# 1-Schematic_SMALL_MODULE.net
KiCad netlist of a schematic drawn in EasyEDA
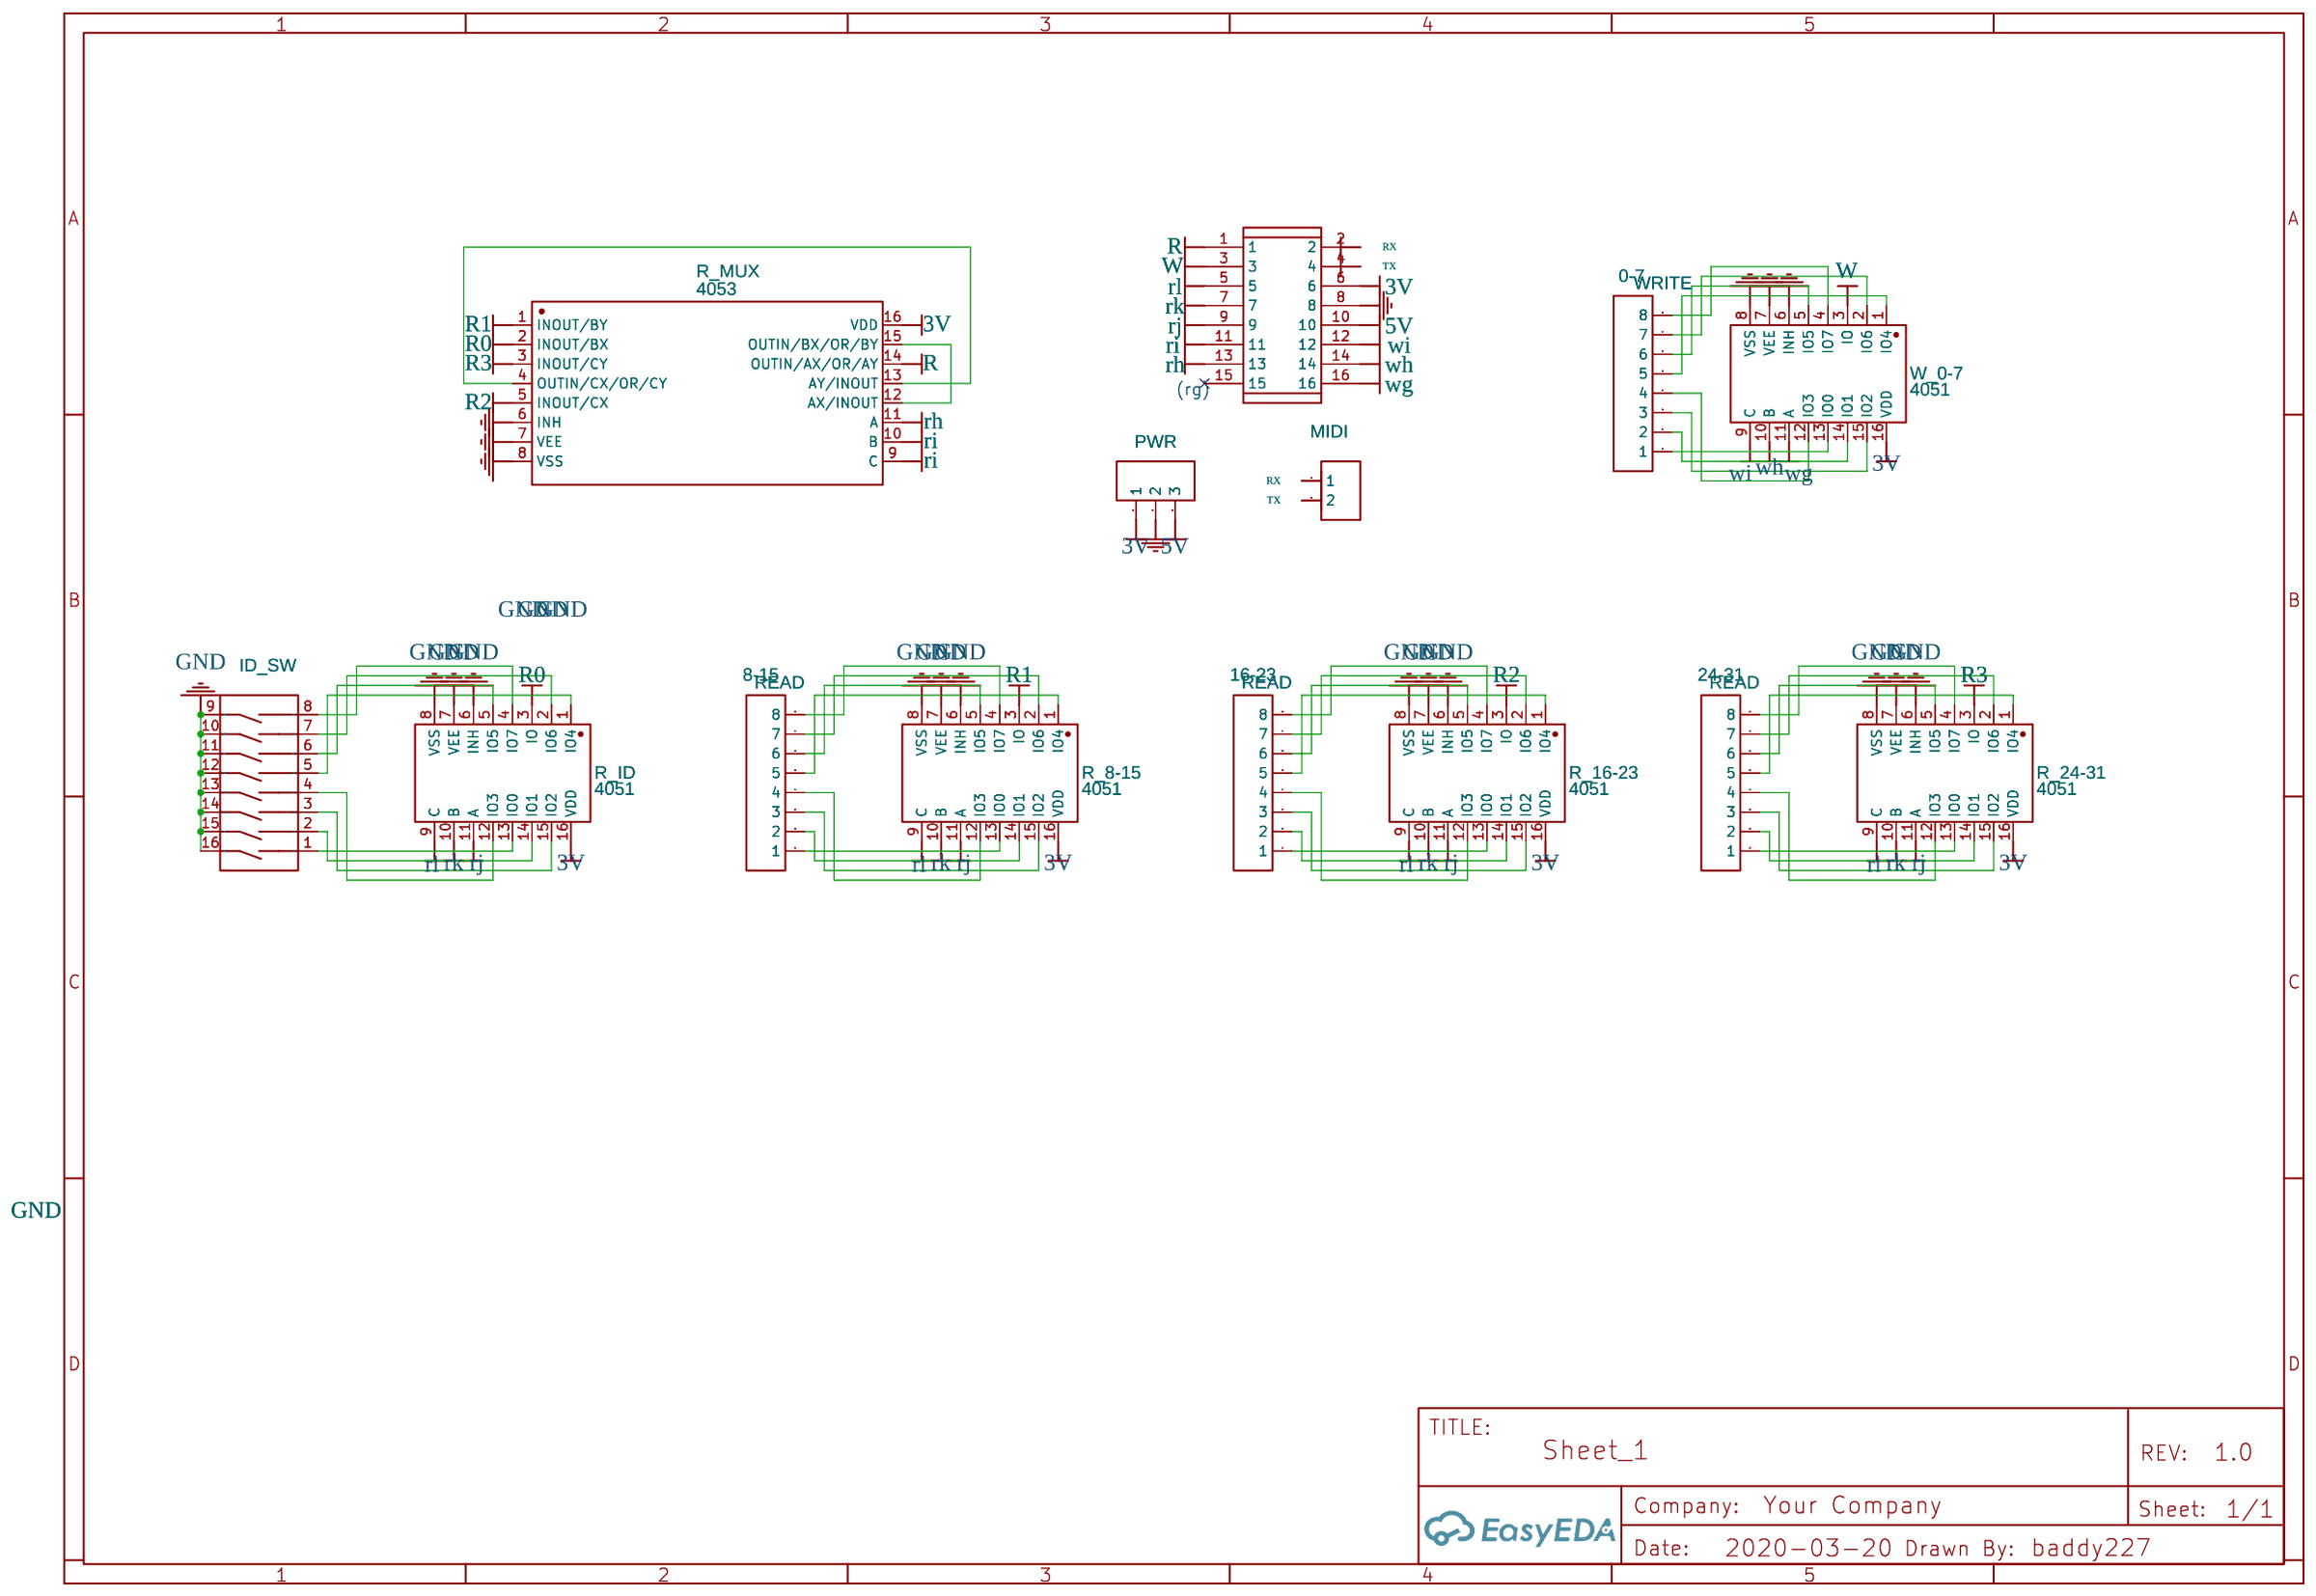
[diagram p0: schematic sheet]

(export (version "E")
  (design (tool "Eeschema 10.0.6"))
  (components
    (comp (ref "0-7")
      (value "WRITE")
      (fields
        (field (name "BOM_Manufacturer Part") "Female headerHDR1X8-2.54")
        (field (name "BOM_Supplier Part") "C27438")
      )
      (libsource (lib "") (part "Header-Female-2.54_1x8_1"))
    )
    (comp (ref "8-15")
      (value "READ")
      (fields
        (field (name "BOM_Manufacturer Part") "Female headerHDR1X8-2.54")
        (field (name "BOM_Supplier Part") "C27438")
      )
      (libsource (lib "") (part "Header-Female-2.54_1x8_2"))
    )
    (comp (ref "16-23")
      (value "READ")
      (fields
        (field (name "BOM_Manufacturer Part") "Female headerHDR1X8-2.54")
        (field (name "BOM_Supplier Part") "C27438")
      )
      (libsource (lib "") (part "Header-Female-2.54_1x8"))
    )
    (comp (ref "24-31")
      (value "READ")
      (fields
        (field (name "BOM_Manufacturer Part") "Female headerHDR1X8-2.54")
        (field (name "BOM_Supplier Part") "C27438")
      )
      (libsource (lib "") (part "Header-Female-2.54_1x8_3"))
    )
    (comp (ref "IDC_16")
      (value "IDC Box 2X8 2.54MM")
      (fields (field (name "BOM_Supplier Part") "C9142"))
      (libsource (lib "") (part "IDC Box 2X8 2.54MM"))
    )
    (comp (ref "ID_SW")
      (value "DIP switchEI-08")
      (fields (field (name "BOM_Supplier Part") "C90019"))
      (libsource (lib "") (part "DIP switchEI-08"))
    )
    (comp (ref "MIDI")
      (value "HDR-M-2.54_1x2")
      (fields (field (name "BOM_Supplier Part") "C124375"))
      (libsource (lib "") (part "HDR-M-2.54_1x2"))
    )
    (comp (ref "PWR")
      (value "Header-Male-2.54_1x3")
      (fields
        (field (name "BOM_Manufacturer Part") "Header2.54mm 1*3P")
        (field (name "BOM_Supplier Part") "C49257")
      )
      (libsource (lib "") (part "Header-Male-2.54_1x3"))
    )
    (comp (ref "R_8-15")
      (value "4051")
      (fields (field (name "BOM_Manufacturer Part") "CD4051BE") (field (name "BOM_Supplier Part") "C5200"))
      (libsource (lib "") (part "CD4051BE"))
    )
    (comp (ref "R_16-23")
      (value "4051")
      (fields (field (name "BOM_Manufacturer Part") "CD4051BE") (field (name "BOM_Supplier Part") "C5200"))
      (libsource (lib "") (part "CD4051BE_1"))
    )
    (comp (ref "R_24-31")
      (value "4051")
      (fields (field (name "BOM_Manufacturer Part") "CD4051BE") (field (name "BOM_Supplier Part") "C5200"))
      (libsource (lib "") (part "CD4051BE_3"))
    )
    (comp (ref "R_ID")
      (value "4051")
      (fields (field (name "BOM_Manufacturer Part") "CD4051BE") (field (name "BOM_Supplier Part") "C5200"))
      (libsource (lib "") (part "CD4051BE_4"))
    )
    (comp (ref "R_MUX")
      (value "4053")
      (fields (field (name "BOM_Manufacturer Part") "CD4053BE") (field (name "BOM_Supplier Part") "C5202"))
      (libsource (lib "") (part "CD4053BE"))
    )
    (comp (ref "W_0-7")
      (value "4051")
      (fields (field (name "BOM_Manufacturer Part") "CD4051BE") (field (name "BOM_Supplier Part") "C5200"))
      (libsource (lib "") (part "CD4051BE_2"))
    )
  )
  (nets
    (net (code "1") (name "3V") (class "Default")
      (node (ref "IDC_16") (pin "6") (pinfunction "6_6") (pintype "unspecified"))
      (node (ref "PWR") (pin "1") (pinfunction "1_1") (pintype "input"))
      (node (ref "R_16-23") (pin "16") (pinfunction "VDD_16") (pintype "unspecified"))
      (node (ref "R_24-31") (pin "16") (pinfunction "VDD_16") (pintype "unspecified"))
      (node (ref "R_8-15") (pin "16") (pinfunction "VDD_16") (pintype "unspecified"))
      (node (ref "R_ID") (pin "16") (pinfunction "VDD_16") (pintype "unspecified"))
      (node (ref "R_MUX") (pin "16") (pinfunction "VDD_16") (pintype "unspecified"))
      (node (ref "W_0-7") (pin "16") (pinfunction "VDD_16") (pintype "unspecified"))
    )
    (net (code "2") (name "5V") (class "Default")
      (node (ref "IDC_16") (pin "10") (pinfunction "10_10") (pintype "unspecified"))
      (node (ref "PWR") (pin "3") (pinfunction "3_3") (pintype "input"))
    )
    (net (code "3") (name "GND") (class "Default")
      (node (ref "IDC_16") (pin "8") (pinfunction "8_8") (pintype "unspecified"))
      (node (ref "ID_SW") (pin "10") (pinfunction "10_10") (pintype "unspecified"))
      (node (ref "ID_SW") (pin "11") (pinfunction "11_11") (pintype "unspecified"))
      (node (ref "ID_SW") (pin "12") (pinfunction "12_12") (pintype "unspecified"))
      (node (ref "ID_SW") (pin "13") (pinfunction "13_13") (pintype "unspecified"))
      (node (ref "ID_SW") (pin "14") (pinfunction "14_14") (pintype "unspecified"))
      (node (ref "ID_SW") (pin "15") (pinfunction "15_15") (pintype "unspecified"))
      (node (ref "ID_SW") (pin "16") (pinfunction "16_16") (pintype "unspecified"))
      (node (ref "ID_SW") (pin "9") (pinfunction "9_9") (pintype "unspecified"))
      (node (ref "PWR") (pin "2") (pinfunction "2_2") (pintype "input"))
      (node (ref "R_16-23") (pin "6") (pinfunction "INH_6") (pintype "unspecified"))
      (node (ref "R_16-23") (pin "7") (pinfunction "VEE_7") (pintype "unspecified"))
      (node (ref "R_16-23") (pin "8") (pinfunction "VSS_8") (pintype "unspecified"))
      (node (ref "R_24-31") (pin "6") (pinfunction "INH_6") (pintype "unspecified"))
      (node (ref "R_24-31") (pin "7") (pinfunction "VEE_7") (pintype "unspecified"))
      (node (ref "R_24-31") (pin "8") (pinfunction "VSS_8") (pintype "unspecified"))
      (node (ref "R_8-15") (pin "6") (pinfunction "INH_6") (pintype "unspecified"))
      (node (ref "R_8-15") (pin "7") (pinfunction "VEE_7") (pintype "unspecified"))
      (node (ref "R_8-15") (pin "8") (pinfunction "VSS_8") (pintype "unspecified"))
      (node (ref "R_ID") (pin "6") (pinfunction "INH_6") (pintype "unspecified"))
      (node (ref "R_ID") (pin "7") (pinfunction "VEE_7") (pintype "unspecified"))
      (node (ref "R_ID") (pin "8") (pinfunction "VSS_8") (pintype "unspecified"))
      (node (ref "R_MUX") (pin "6") (pinfunction "INH_6") (pintype "unspecified"))
      (node (ref "R_MUX") (pin "7") (pinfunction "VEE_7") (pintype "unspecified"))
      (node (ref "R_MUX") (pin "8") (pinfunction "VSS_8") (pintype "unspecified"))
      (node (ref "W_0-7") (pin "6") (pinfunction "INH_6") (pintype "unspecified"))
      (node (ref "W_0-7") (pin "7") (pinfunction "VEE_7") (pintype "unspecified"))
      (node (ref "W_0-7") (pin "8") (pinfunction "VSS_8") (pintype "unspecified"))
    )
    (net (code "4") (name "Net-(R_8-15-IO0)") (class "Default")
      (node (ref "8-15") (pin "1") (pinfunction "1_1") (pintype "input"))
      (node (ref "R_8-15") (pin "13") (pinfunction "IO0_13") (pintype "unspecified"))
    )
    (net (code "5") (name "Net-(R_8-15-IO1)") (class "Default")
      (node (ref "8-15") (pin "2") (pinfunction "2_2") (pintype "input"))
      (node (ref "R_8-15") (pin "14") (pinfunction "IO1_14") (pintype "unspecified"))
    )
    (net (code "6") (name "Net-(R_8-15-IO2)") (class "Default")
      (node (ref "8-15") (pin "3") (pinfunction "3_3") (pintype "input"))
      (node (ref "R_8-15") (pin "15") (pinfunction "IO2_15") (pintype "unspecified"))
    )
    (net (code "7") (name "Net-(R_8-15-IO3)") (class "Default")
      (node (ref "8-15") (pin "4") (pinfunction "4_4") (pintype "input"))
      (node (ref "R_8-15") (pin "12") (pinfunction "IO3_12") (pintype "unspecified"))
    )
    (net (code "8") (name "Net-(R_8-15-IO4)") (class "Default")
      (node (ref "8-15") (pin "5") (pinfunction "5_5") (pintype "input"))
      (node (ref "R_8-15") (pin "1") (pinfunction "IO4_1") (pintype "unspecified"))
    )
    (net (code "9") (name "Net-(R_8-15-IO5)") (class "Default")
      (node (ref "8-15") (pin "6") (pinfunction "6_6") (pintype "input"))
      (node (ref "R_8-15") (pin "5") (pinfunction "IO5_5") (pintype "unspecified"))
    )
    (net (code "10") (name "Net-(R_8-15-IO6)") (class "Default")
      (node (ref "8-15") (pin "7") (pinfunction "7_7") (pintype "input"))
      (node (ref "R_8-15") (pin "2") (pinfunction "IO6_2") (pintype "unspecified"))
    )
    (net (code "11") (name "Net-(R_8-15-IO7)") (class "Default")
      (node (ref "8-15") (pin "8") (pinfunction "8_8") (pintype "input"))
      (node (ref "R_8-15") (pin "4") (pinfunction "IO7_4") (pintype "unspecified"))
    )
    (net (code "12") (name "Net-(R_16-23-IO0)") (class "Default")
      (node (ref "16-23") (pin "1") (pinfunction "1_1") (pintype "input"))
      (node (ref "R_16-23") (pin "13") (pinfunction "IO0_13") (pintype "unspecified"))
    )
    (net (code "13") (name "Net-(R_16-23-IO1)") (class "Default")
      (node (ref "16-23") (pin "2") (pinfunction "2_2") (pintype "input"))
      (node (ref "R_16-23") (pin "14") (pinfunction "IO1_14") (pintype "unspecified"))
    )
    (net (code "14") (name "Net-(R_16-23-IO2)") (class "Default")
      (node (ref "16-23") (pin "3") (pinfunction "3_3") (pintype "input"))
      (node (ref "R_16-23") (pin "15") (pinfunction "IO2_15") (pintype "unspecified"))
    )
    (net (code "15") (name "Net-(R_16-23-IO3)") (class "Default")
      (node (ref "16-23") (pin "4") (pinfunction "4_4") (pintype "input"))
      (node (ref "R_16-23") (pin "12") (pinfunction "IO3_12") (pintype "unspecified"))
    )
    (net (code "16") (name "Net-(R_16-23-IO4)") (class "Default")
      (node (ref "16-23") (pin "5") (pinfunction "5_5") (pintype "input"))
      (node (ref "R_16-23") (pin "1") (pinfunction "IO4_1") (pintype "unspecified"))
    )
    (net (code "17") (name "Net-(R_16-23-IO5)") (class "Default")
      (node (ref "16-23") (pin "6") (pinfunction "6_6") (pintype "input"))
      (node (ref "R_16-23") (pin "5") (pinfunction "IO5_5") (pintype "unspecified"))
    )
    (net (code "18") (name "Net-(R_16-23-IO6)") (class "Default")
      (node (ref "16-23") (pin "7") (pinfunction "7_7") (pintype "input"))
      (node (ref "R_16-23") (pin "2") (pinfunction "IO6_2") (pintype "unspecified"))
    )
    (net (code "19") (name "Net-(R_16-23-IO7)") (class "Default")
      (node (ref "16-23") (pin "8") (pinfunction "8_8") (pintype "input"))
      (node (ref "R_16-23") (pin "4") (pinfunction "IO7_4") (pintype "unspecified"))
    )
    (net (code "20") (name "Net-(R_24-31-IO0)") (class "Default")
      (node (ref "24-31") (pin "1") (pinfunction "1_1") (pintype "input"))
      (node (ref "R_24-31") (pin "13") (pinfunction "IO0_13") (pintype "unspecified"))
    )
    (net (code "21") (name "Net-(R_24-31-IO1)") (class "Default")
      (node (ref "24-31") (pin "2") (pinfunction "2_2") (pintype "input"))
      (node (ref "R_24-31") (pin "14") (pinfunction "IO1_14") (pintype "unspecified"))
    )
    (net (code "22") (name "Net-(R_24-31-IO2)") (class "Default")
      (node (ref "24-31") (pin "3") (pinfunction "3_3") (pintype "input"))
      (node (ref "R_24-31") (pin "15") (pinfunction "IO2_15") (pintype "unspecified"))
    )
    (net (code "23") (name "Net-(R_24-31-IO3)") (class "Default")
      (node (ref "24-31") (pin "4") (pinfunction "4_4") (pintype "input"))
      (node (ref "R_24-31") (pin "12") (pinfunction "IO3_12") (pintype "unspecified"))
    )
    (net (code "24") (name "Net-(R_24-31-IO4)") (class "Default")
      (node (ref "24-31") (pin "5") (pinfunction "5_5") (pintype "input"))
      (node (ref "R_24-31") (pin "1") (pinfunction "IO4_1") (pintype "unspecified"))
    )
    (net (code "25") (name "Net-(R_24-31-IO5)") (class "Default")
      (node (ref "24-31") (pin "6") (pinfunction "6_6") (pintype "input"))
      (node (ref "R_24-31") (pin "5") (pinfunction "IO5_5") (pintype "unspecified"))
    )
    (net (code "26") (name "Net-(R_24-31-IO6)") (class "Default")
      (node (ref "24-31") (pin "7") (pinfunction "7_7") (pintype "input"))
      (node (ref "R_24-31") (pin "2") (pinfunction "IO6_2") (pintype "unspecified"))
    )
    (net (code "27") (name "Net-(R_24-31-IO7)") (class "Default")
      (node (ref "24-31") (pin "8") (pinfunction "8_8") (pintype "input"))
      (node (ref "R_24-31") (pin "4") (pinfunction "IO7_4") (pintype "unspecified"))
    )
    (net (code "28") (name "Net-(R_ID-IO0)") (class "Default")
      (node (ref "ID_SW") (pin "1") (pinfunction "1_1") (pintype "unspecified"))
      (node (ref "R_ID") (pin "13") (pinfunction "IO0_13") (pintype "unspecified"))
    )
    (net (code "29") (name "Net-(R_ID-IO1)") (class "Default")
      (node (ref "ID_SW") (pin "2") (pinfunction "2_2") (pintype "unspecified"))
      (node (ref "R_ID") (pin "14") (pinfunction "IO1_14") (pintype "unspecified"))
    )
    (net (code "30") (name "Net-(R_ID-IO2)") (class "Default")
      (node (ref "ID_SW") (pin "3") (pinfunction "3_3") (pintype "unspecified"))
      (node (ref "R_ID") (pin "15") (pinfunction "IO2_15") (pintype "unspecified"))
    )
    (net (code "31") (name "Net-(R_ID-IO3)") (class "Default")
      (node (ref "ID_SW") (pin "4") (pinfunction "4_4") (pintype "unspecified"))
      (node (ref "R_ID") (pin "12") (pinfunction "IO3_12") (pintype "unspecified"))
    )
    (net (code "32") (name "Net-(R_ID-IO4)") (class "Default")
      (node (ref "ID_SW") (pin "5") (pinfunction "5_5") (pintype "unspecified"))
      (node (ref "R_ID") (pin "1") (pinfunction "IO4_1") (pintype "unspecified"))
    )
    (net (code "33") (name "Net-(R_ID-IO5)") (class "Default")
      (node (ref "ID_SW") (pin "6") (pinfunction "6_6") (pintype "unspecified"))
      (node (ref "R_ID") (pin "5") (pinfunction "IO5_5") (pintype "unspecified"))
    )
    (net (code "34") (name "Net-(R_ID-IO6)") (class "Default")
      (node (ref "ID_SW") (pin "7") (pinfunction "7_7") (pintype "unspecified"))
      (node (ref "R_ID") (pin "2") (pinfunction "IO6_2") (pintype "unspecified"))
    )
    (net (code "35") (name "Net-(R_ID-IO7)") (class "Default")
      (node (ref "ID_SW") (pin "8") (pinfunction "8_8") (pintype "unspecified"))
      (node (ref "R_ID") (pin "4") (pinfunction "IO7_4") (pintype "unspecified"))
    )
    (net (code "36") (name "Net-(R_MUX-AX{slash}INOUT)") (class "Default")
      (node (ref "R_MUX") (pin "12") (pinfunction "AX/INOUT_12") (pintype "unspecified"))
      (node (ref "R_MUX") (pin "15") (pinfunction "OUTIN/BX/OR/BY_15") (pintype "unspecified"))
    )
    (net (code "37") (name "Net-(R_MUX-AY{slash}INOUT)") (class "Default")
      (node (ref "R_MUX") (pin "13") (pinfunction "AY/INOUT_13") (pintype "unspecified"))
      (node (ref "R_MUX") (pin "4") (pinfunction "OUTIN/CX/OR/CY_4") (pintype "unspecified"))
    )
    (net (code "38") (name "Net-(W_0-7-IO0)") (class "Default")
      (node (ref "0-7") (pin "1") (pinfunction "1_1") (pintype "input"))
      (node (ref "W_0-7") (pin "13") (pinfunction "IO0_13") (pintype "unspecified"))
    )
    (net (code "39") (name "Net-(W_0-7-IO1)") (class "Default")
      (node (ref "0-7") (pin "2") (pinfunction "2_2") (pintype "input"))
      (node (ref "W_0-7") (pin "14") (pinfunction "IO1_14") (pintype "unspecified"))
    )
    (net (code "40") (name "Net-(W_0-7-IO2)") (class "Default")
      (node (ref "0-7") (pin "3") (pinfunction "3_3") (pintype "input"))
      (node (ref "W_0-7") (pin "15") (pinfunction "IO2_15") (pintype "unspecified"))
    )
    (net (code "41") (name "Net-(W_0-7-IO3)") (class "Default")
      (node (ref "0-7") (pin "4") (pinfunction "4_4") (pintype "input"))
      (node (ref "W_0-7") (pin "12") (pinfunction "IO3_12") (pintype "unspecified"))
    )
    (net (code "42") (name "Net-(W_0-7-IO4)") (class "Default")
      (node (ref "0-7") (pin "5") (pinfunction "5_5") (pintype "input"))
      (node (ref "W_0-7") (pin "1") (pinfunction "IO4_1") (pintype "unspecified"))
    )
    (net (code "43") (name "Net-(W_0-7-IO5)") (class "Default")
      (node (ref "0-7") (pin "6") (pinfunction "6_6") (pintype "input"))
      (node (ref "W_0-7") (pin "5") (pinfunction "IO5_5") (pintype "unspecified"))
    )
    (net (code "44") (name "Net-(W_0-7-IO6)") (class "Default")
      (node (ref "0-7") (pin "7") (pinfunction "7_7") (pintype "input"))
      (node (ref "W_0-7") (pin "2") (pinfunction "IO6_2") (pintype "unspecified"))
    )
    (net (code "45") (name "Net-(W_0-7-IO7)") (class "Default")
      (node (ref "0-7") (pin "8") (pinfunction "8_8") (pintype "input"))
      (node (ref "W_0-7") (pin "4") (pinfunction "IO7_4") (pintype "unspecified"))
    )
    (net (code "46") (name "R") (class "Default")
      (node (ref "IDC_16") (pin "1") (pinfunction "1_1") (pintype "unspecified"))
      (node (ref "R_MUX") (pin "14") (pinfunction "OUTIN/AX/OR/AY_14") (pintype "unspecified"))
    )
    (net (code "47") (name "R0") (class "Default")
      (node (ref "R_ID") (pin "3") (pinfunction "IO_3") (pintype "unspecified"))
      (node (ref "R_MUX") (pin "2") (pinfunction "INOUT/BX_2") (pintype "unspecified"))
    )
    (net (code "48") (name "R1") (class "Default")
      (node (ref "R_8-15") (pin "3") (pinfunction "IO_3") (pintype "unspecified"))
      (node (ref "R_MUX") (pin "1") (pinfunction "INOUT/BY_1") (pintype "unspecified"))
    )
    (net (code "49") (name "R2") (class "Default")
      (node (ref "R_16-23") (pin "3") (pinfunction "IO_3") (pintype "unspecified"))
      (node (ref "R_MUX") (pin "5") (pinfunction "INOUT/CX_5") (pintype "unspecified"))
    )
    (net (code "50") (name "R3") (class "Default")
      (node (ref "R_24-31") (pin "3") (pinfunction "IO_3") (pintype "unspecified"))
      (node (ref "R_MUX") (pin "3") (pinfunction "INOUT/CY_3") (pintype "unspecified"))
    )
    (net (code "51") (name "RX") (class "Default")
      (node (ref "IDC_16") (pin "2") (pinfunction "2_2") (pintype "unspecified"))
      (node (ref "MIDI") (pin "1") (pinfunction "1_1") (pintype "unspecified"))
    )
    (net (code "52") (name "TX") (class "Default")
      (node (ref "IDC_16") (pin "4") (pinfunction "4_4") (pintype "unspecified"))
      (node (ref "MIDI") (pin "2") (pinfunction "2_2") (pintype "unspecified"))
    )
    (net (code "53") (name "W") (class "Default")
      (node (ref "IDC_16") (pin "3") (pinfunction "3_3") (pintype "unspecified"))
      (node (ref "W_0-7") (pin "3") (pinfunction "IO_3") (pintype "unspecified"))
    )
    (net (code "54") (name "rh") (class "Default")
      (node (ref "IDC_16") (pin "13") (pinfunction "13_13") (pintype "unspecified"))
      (node (ref "R_MUX") (pin "11") (pinfunction "A_11") (pintype "unspecified"))
    )
    (net (code "55") (name "ri") (class "Default")
      (node (ref "IDC_16") (pin "11") (pinfunction "11_11") (pintype "unspecified"))
      (node (ref "R_MUX") (pin "10") (pinfunction "B_10") (pintype "unspecified"))
      (node (ref "R_MUX") (pin "9") (pinfunction "C_9") (pintype "unspecified"))
    )
    (net (code "56") (name "rj") (class "Default")
      (node (ref "IDC_16") (pin "9") (pinfunction "9_9") (pintype "unspecified"))
      (node (ref "R_16-23") (pin "11") (pinfunction "A_11") (pintype "unspecified"))
      (node (ref "R_24-31") (pin "11") (pinfunction "A_11") (pintype "unspecified"))
      (node (ref "R_8-15") (pin "11") (pinfunction "A_11") (pintype "unspecified"))
      (node (ref "R_ID") (pin "11") (pinfunction "A_11") (pintype "unspecified"))
    )
    (net (code "57") (name "rk") (class "Default")
      (node (ref "IDC_16") (pin "7") (pinfunction "7_7") (pintype "unspecified"))
      (node (ref "R_16-23") (pin "10") (pinfunction "B_10") (pintype "unspecified"))
      (node (ref "R_24-31") (pin "10") (pinfunction "B_10") (pintype "unspecified"))
      (node (ref "R_8-15") (pin "10") (pinfunction "B_10") (pintype "unspecified"))
      (node (ref "R_ID") (pin "10") (pinfunction "B_10") (pintype "unspecified"))
    )
    (net (code "58") (name "rl") (class "Default")
      (node (ref "IDC_16") (pin "5") (pinfunction "5_5") (pintype "unspecified"))
      (node (ref "R_16-23") (pin "9") (pinfunction "C_9") (pintype "unspecified"))
      (node (ref "R_24-31") (pin "9") (pinfunction "C_9") (pintype "unspecified"))
      (node (ref "R_8-15") (pin "9") (pinfunction "C_9") (pintype "unspecified"))
      (node (ref "R_ID") (pin "9") (pinfunction "C_9") (pintype "unspecified"))
    )
    (net (code "59") (name "unconnected-(IDC_16-Pad15)") (class "Default")
      (node (ref "IDC_16") (pin "15") (pinfunction "15_15") (pintype "unspecified+no_connect"))
    )
    (net (code "60") (name "wg") (class "Default")
      (node (ref "IDC_16") (pin "16") (pinfunction "16_16") (pintype "unspecified"))
      (node (ref "W_0-7") (pin "11") (pinfunction "A_11") (pintype "unspecified"))
    )
    (net (code "61") (name "wh") (class "Default")
      (node (ref "IDC_16") (pin "14") (pinfunction "14_14") (pintype "unspecified"))
      (node (ref "W_0-7") (pin "10") (pinfunction "B_10") (pintype "unspecified"))
    )
    (net (code "62") (name "wi") (class "Default")
      (node (ref "IDC_16") (pin "12") (pinfunction "12_12") (pintype "unspecified"))
      (node (ref "W_0-7") (pin "9") (pinfunction "C_9") (pintype "unspecified"))
    )
  )
)
